# pearwatch-bottom.net
KiCad netlist of a schematic drawn in EAGLE
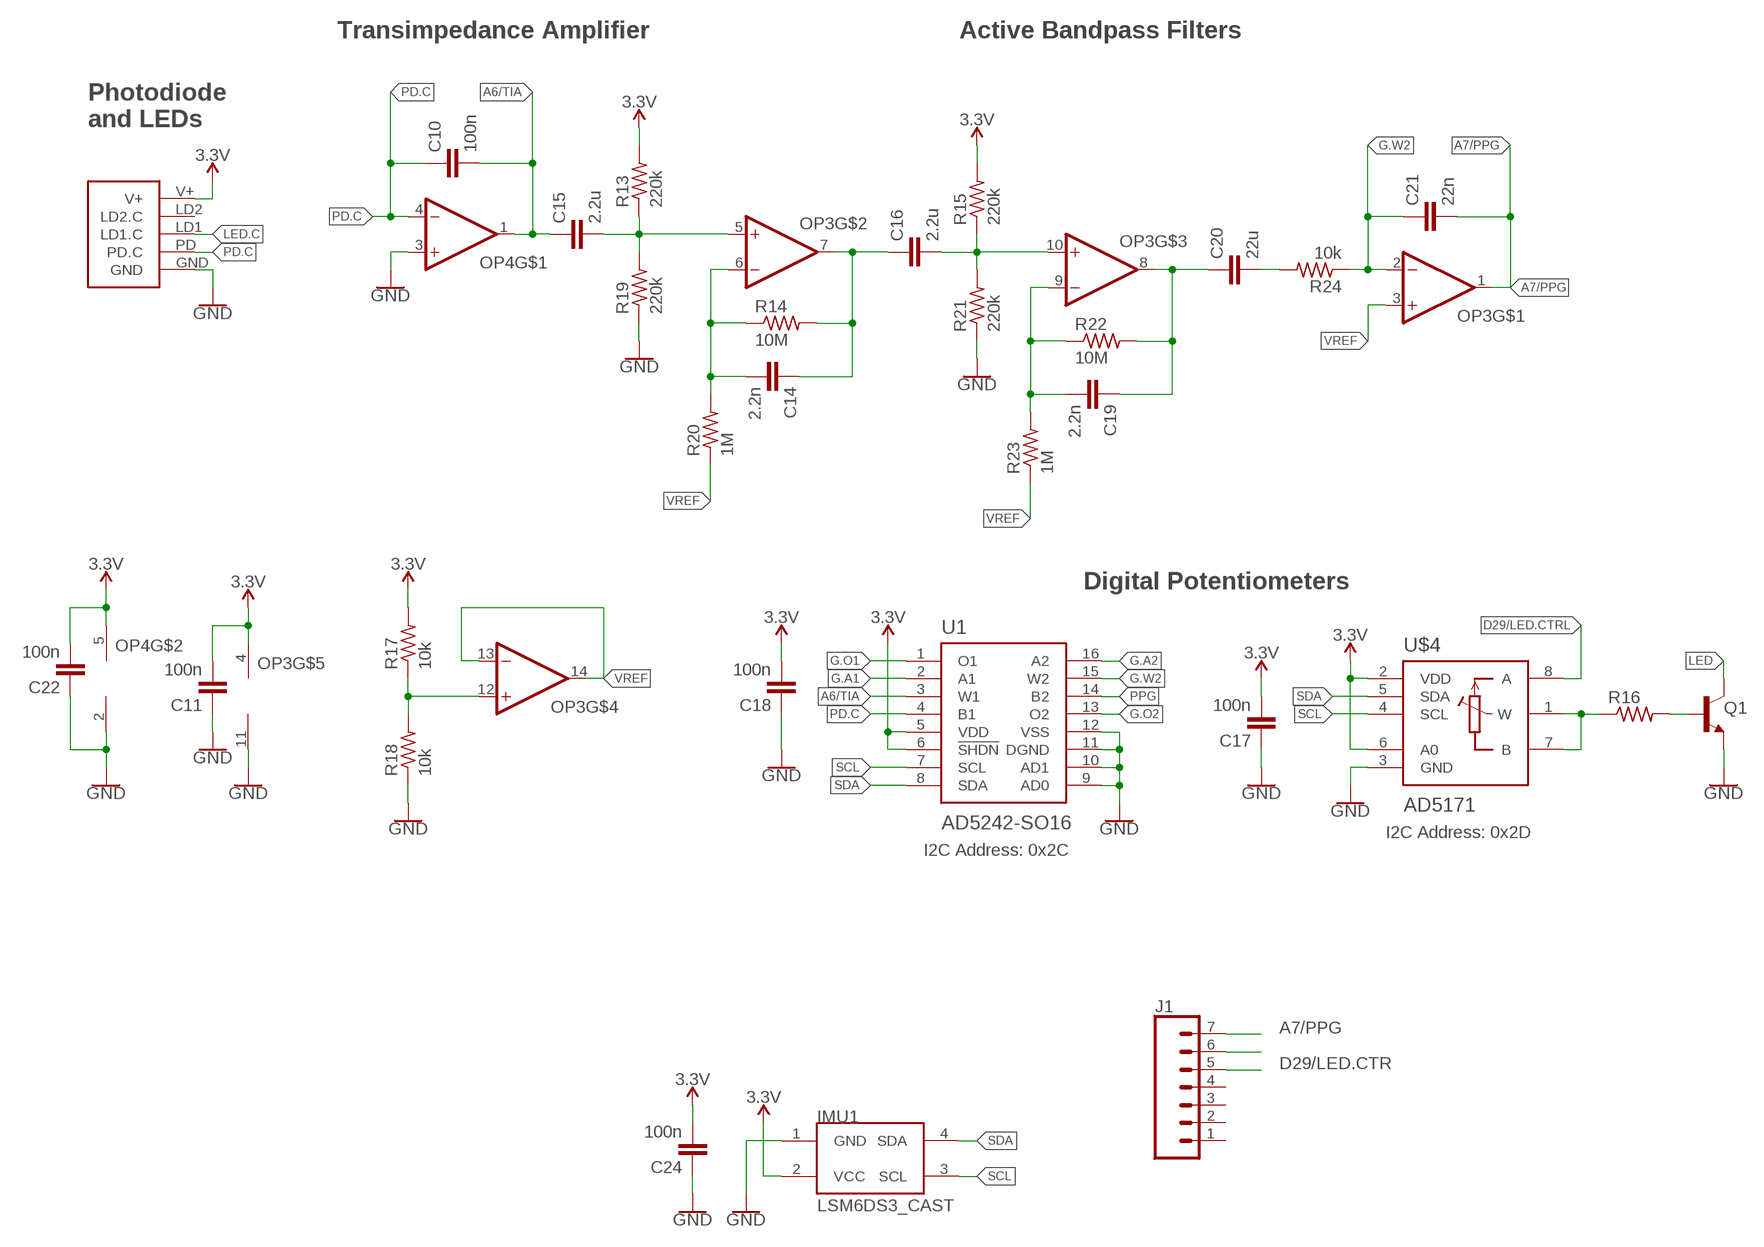
[diagram p0: schematic, sheet 1]

(export (version "E")
  (design (tool "Eeschema 10.0.6"))
  (components
    (comp (ref "C10")
      (value "100n")
      (footprint "eagle-import:C0603")
      (libsource (lib "eagle-import") (part "CAPACITOR0603"))
    )
    (comp (ref "C11")
      (value "100n")
      (footprint "eagle-import:C0603")
      (libsource (lib "eagle-import") (part "CAPACITOR0603"))
    )
    (comp (ref "C14")
      (value "2.2n")
      (footprint "eagle-import:C0603")
      (libsource (lib "eagle-import") (part "CAPACITOR0603"))
    )
    (comp (ref "C15")
      (value "2.2u")
      (footprint "eagle-import:C0603")
      (libsource (lib "eagle-import") (part "CAPACITOR0603"))
    )
    (comp (ref "C16")
      (value "2.2u")
      (footprint "eagle-import:C0603")
      (libsource (lib "eagle-import") (part "CAPACITOR0603"))
    )
    (comp (ref "C17")
      (value "100n")
      (footprint "eagle-import:C0603")
      (libsource (lib "eagle-import") (part "CAPACITOR0603"))
    )
    (comp (ref "C18")
      (value "100n")
      (footprint "eagle-import:C0603")
      (libsource (lib "eagle-import") (part "CAPACITOR0603"))
    )
    (comp (ref "C19")
      (value "2.2n")
      (footprint "eagle-import:C0603")
      (libsource (lib "eagle-import") (part "CAPACITOR0603"))
    )
    (comp (ref "C20")
      (value "22u")
      (footprint "eagle-import:C0603")
      (libsource (lib "eagle-import") (part "CAPACITOR0603"))
    )
    (comp (ref "C21")
      (value "22n")
      (footprint "eagle-import:C0603")
      (libsource (lib "eagle-import") (part "CAPACITOR0603"))
    )
    (comp (ref "C22")
      (value "100n")
      (footprint "eagle-import:C0603")
      (libsource (lib "eagle-import") (part "CAPACITOR0603"))
    )
    (comp (ref "C24")
      (value "100n")
      (footprint "eagle-import:C0603")
      (libsource (lib "eagle-import") (part "CAPACITOR0603"))
    )
    (comp (ref "IMU1")
      (value "LSM6DS3_CAST")
      (footprint "eagle-import:LSM6DS3_CAST")
      (libsource (lib "eagle-import") (part "LSM6DS3_CAST"))
    )
    (comp (ref "J1")
      (value "CONN_07")
      (footprint "eagle-import:1X07")
      (libsource (lib "eagle-import") (part "CONN_07"))
    )
    (comp (ref "OP3")
      (value "OP-QUAD-SO14")
      (footprint "eagle-import:SO14")
      (libsource (lib "eagle-import") (part "OP-QUAD-SO14"))
    )
    (comp (ref "OP4")
      (value "OP-SINGLEOT")
      (footprint "eagle-import:SOT23-5")
      (libsource (lib "eagle-import") (part "OP-SINGLEOT"))
    )
    (comp (ref "Q1")
      (value "NPN-GENERIC")
      (footprint "eagle-import:SOT23-3")
      (libsource (lib "eagle-import") (part "NPN-GENERIC"))
    )
    (comp (ref "R13")
      (value "220k")
      (footprint "eagle-import:R0603")
      (libsource (lib "eagle-import") (part "RESISTOR0603"))
    )
    (comp (ref "R14")
      (value "10M")
      (footprint "eagle-import:R0603")
      (libsource (lib "eagle-import") (part "RESISTOR0603"))
    )
    (comp (ref "R15")
      (value "220k")
      (footprint "eagle-import:R0603")
      (libsource (lib "eagle-import") (part "RESISTOR0603"))
    )
    (comp (ref "R16")
      (value "RESISTOR0603")
      (footprint "eagle-import:R0603")
      (libsource (lib "eagle-import") (part "RESISTOR0603"))
    )
    (comp (ref "R17")
      (value "10k")
      (footprint "eagle-import:R0402")
      (libsource (lib "eagle-import") (part "RESISTOR0402"))
    )
    (comp (ref "R18")
      (value "10k")
      (footprint "eagle-import:R0402")
      (libsource (lib "eagle-import") (part "RESISTOR0402"))
    )
    (comp (ref "R19")
      (value "220k")
      (footprint "eagle-import:R0603")
      (libsource (lib "eagle-import") (part "RESISTOR0603"))
    )
    (comp (ref "R20")
      (value "1M")
      (footprint "eagle-import:R0603")
      (libsource (lib "eagle-import") (part "RESISTOR0603"))
    )
    (comp (ref "R21")
      (value "220k")
      (footprint "eagle-import:R0603")
      (libsource (lib "eagle-import") (part "RESISTOR0603"))
    )
    (comp (ref "R22")
      (value "10M")
      (footprint "eagle-import:R0603")
      (libsource (lib "eagle-import") (part "RESISTOR0603"))
    )
    (comp (ref "R23")
      (value "1M")
      (footprint "eagle-import:R0603")
      (libsource (lib "eagle-import") (part "RESISTOR0603"))
    )
    (comp (ref "R24")
      (value "10k")
      (footprint "eagle-import:R0603")
      (libsource (lib "eagle-import") (part "RESISTOR0603"))
    )
    (comp (ref "U$3")
      (value "PPG.MODULE.2")
      (footprint "eagle-import:PPG.MODULE.2")
      (libsource (lib "eagle-import") (part "PPG.MODULE.2"))
    )
    (comp (ref "U$4")
      (value "AD5171")
      (footprint "eagle-import:SOT-23-8")
      (libsource (lib "eagle-import") (part "AD5171"))
    )
    (comp (ref "U1")
      (value "AD5242-SO16")
      (footprint "eagle-import:SO16")
      (libsource (lib "eagle-import") (part "AD5242-SO16"))
    )
  )
  (nets
    (net (code "1") (name "/D29{slash}LED.CTR") (class "Default")
      (node (ref "J1") (pin "6") (pinfunction "6_6") (pintype "passive"))
    )
    (net (code "2") (name "3.3V") (class "Default")
      (node (ref "C11") (pin "2") (pinfunction "2_2") (pintype "passive"))
      (node (ref "C17") (pin "2") (pinfunction "2_2") (pintype "passive"))
      (node (ref "C18") (pin "2") (pinfunction "2_2") (pintype "passive"))
      (node (ref "C22") (pin "2") (pinfunction "2_2") (pintype "passive"))
      (node (ref "C24") (pin "2") (pinfunction "2_2") (pintype "passive"))
      (node (ref "IMU1") (pin "2") (pinfunction "VCC_2") (pintype "bidirectional"))
      (node (ref "OP3") (pin "4") (pinfunction "V+_4") (pintype "power_in"))
      (node (ref "OP4") (pin "5") (pinfunction "V+_5") (pintype "power_in"))
      (node (ref "R13") (pin "2") (pinfunction "2_2") (pintype "passive"))
      (node (ref "R15") (pin "2") (pinfunction "2_2") (pintype "passive"))
      (node (ref "R17") (pin "2") (pinfunction "2_2") (pintype "passive"))
      (node (ref "U$3") (pin "V+") (pinfunction "V+_V+") (pintype "bidirectional"))
      (node (ref "U$4") (pin "2") (pinfunction "VDD_2") (pintype "bidirectional"))
      (node (ref "U$4") (pin "6") (pinfunction "A0_6") (pintype "bidirectional"))
      (node (ref "U1") (pin "5") (pinfunction "VDD_5") (pintype "bidirectional"))
      (node (ref "U1") (pin "6") (pinfunction "~{SHDN}_6") (pintype "bidirectional"))
    )
    (net (code "3") (name "A6{slash}TIA") (class "Default")
      (node (ref "C10") (pin "2") (pinfunction "2_2") (pintype "passive"))
      (node (ref "C15") (pin "1") (pinfunction "1_1") (pintype "passive"))
      (node (ref "J1") (pin "5") (pinfunction "5_5") (pintype "passive"))
      (node (ref "OP4") (pin "1") (pinfunction "OUT_1") (pintype "output"))
      (node (ref "U1") (pin "3") (pinfunction "W1_3") (pintype "bidirectional"))
    )
    (net (code "4") (name "A7{slash}PPG") (class "Default")
      (node (ref "C21") (pin "2") (pinfunction "2_2") (pintype "passive"))
      (node (ref "J1") (pin "7") (pinfunction "7_7") (pintype "passive"))
      (node (ref "OP3") (pin "1") (pinfunction "OUT_1") (pintype "output"))
    )
    (net (code "5") (name "D29{slash}LED.CTRL") (class "Default")
      (node (ref "U$4") (pin "8") (pinfunction "A_8") (pintype "bidirectional"))
    )
    (net (code "6") (name "G.A1") (class "Default")
      (node (ref "U1") (pin "2") (pinfunction "A1_2") (pintype "bidirectional"))
    )
    (net (code "7") (name "G.A2") (class "Default")
      (node (ref "U1") (pin "16") (pinfunction "A2_16") (pintype "bidirectional"))
    )
    (net (code "8") (name "G.O1") (class "Default")
      (node (ref "U1") (pin "1") (pinfunction "O1_1") (pintype "bidirectional"))
    )
    (net (code "9") (name "G.O2") (class "Default")
      (node (ref "U1") (pin "13") (pinfunction "O2_13") (pintype "bidirectional"))
    )
    (net (code "10") (name "G.W2") (class "Default")
      (node (ref "C21") (pin "1") (pinfunction "1_1") (pintype "passive"))
      (node (ref "OP3") (pin "2") (pinfunction "-IN_2") (pintype "input"))
      (node (ref "R24") (pin "1") (pinfunction "1_1") (pintype "passive"))
      (node (ref "U1") (pin "15") (pinfunction "W2_15") (pintype "bidirectional"))
    )
    (net (code "11") (name "GND") (class "Default")
      (node (ref "C11") (pin "1") (pinfunction "1_1") (pintype "passive"))
      (node (ref "C17") (pin "1") (pinfunction "1_1") (pintype "passive"))
      (node (ref "C18") (pin "1") (pinfunction "1_1") (pintype "passive"))
      (node (ref "C22") (pin "1") (pinfunction "1_1") (pintype "passive"))
      (node (ref "C24") (pin "1") (pinfunction "1_1") (pintype "passive"))
      (node (ref "IMU1") (pin "1") (pinfunction "GND_1") (pintype "bidirectional"))
      (node (ref "OP3") (pin "11") (pinfunction "V-_11") (pintype "power_in"))
      (node (ref "OP4") (pin "2") (pinfunction "V-_2") (pintype "power_in"))
      (node (ref "OP4") (pin "3") (pinfunction "+IN_3") (pintype "input"))
      (node (ref "Q1") (pin "2") (pinfunction "E_2") (pintype "passive"))
      (node (ref "R18") (pin "1") (pinfunction "1_1") (pintype "passive"))
      (node (ref "R19") (pin "1") (pinfunction "1_1") (pintype "passive"))
      (node (ref "R21") (pin "1") (pinfunction "1_1") (pintype "passive"))
      (node (ref "U$3") (pin "GND") (pinfunction "GND_GND") (pintype "bidirectional"))
      (node (ref "U$4") (pin "3") (pinfunction "GND_3") (pintype "bidirectional"))
      (node (ref "U1") (pin "10") (pinfunction "AD1_10") (pintype "bidirectional"))
      (node (ref "U1") (pin "11") (pinfunction "DGND_11") (pintype "bidirectional"))
      (node (ref "U1") (pin "12") (pinfunction "VSS_12") (pintype "bidirectional"))
      (node (ref "U1") (pin "9") (pinfunction "AD0_9") (pintype "bidirectional"))
    )
    (net (code "12") (name "LED") (class "Default")
      (node (ref "Q1") (pin "3") (pinfunction "C_3") (pintype "passive"))
    )
    (net (code "13") (name "LED.C") (class "Default")
      (node (ref "U$3") (pin "LD1") (pinfunction "LD1.C_LD1") (pintype "bidirectional"))
    )
    (net (code "14") (name "Net-(C20-Pad2)") (class "Default")
      (node (ref "C20") (pin "2") (pinfunction "2_2") (pintype "passive"))
      (node (ref "R24") (pin "2") (pinfunction "2_2") (pintype "passive"))
    )
    (net (code "15") (name "Net-(OP3B-+IN)") (class "Default")
      (node (ref "C15") (pin "2") (pinfunction "2_2") (pintype "passive"))
      (node (ref "OP3") (pin "5") (pinfunction "+IN_5") (pintype "input"))
      (node (ref "R13") (pin "1") (pinfunction "1_1") (pintype "passive"))
      (node (ref "R19") (pin "2") (pinfunction "2_2") (pintype "passive"))
    )
    (net (code "16") (name "Net-(OP3B--IN)") (class "Default")
      (node (ref "C14") (pin "2") (pinfunction "2_2") (pintype "passive"))
      (node (ref "OP3") (pin "6") (pinfunction "-IN_6") (pintype "input"))
      (node (ref "R14") (pin "1") (pinfunction "1_1") (pintype "passive"))
      (node (ref "R20") (pin "2") (pinfunction "2_2") (pintype "passive"))
    )
    (net (code "17") (name "Net-(OP3B-OUT)") (class "Default")
      (node (ref "C14") (pin "1") (pinfunction "1_1") (pintype "passive"))
      (node (ref "C16") (pin "1") (pinfunction "1_1") (pintype "passive"))
      (node (ref "OP3") (pin "7") (pinfunction "OUT_7") (pintype "output"))
      (node (ref "R14") (pin "2") (pinfunction "2_2") (pintype "passive"))
    )
    (net (code "18") (name "Net-(OP3C-+IN)") (class "Default")
      (node (ref "C16") (pin "2") (pinfunction "2_2") (pintype "passive"))
      (node (ref "OP3") (pin "10") (pinfunction "+IN_10") (pintype "input"))
      (node (ref "R15") (pin "1") (pinfunction "1_1") (pintype "passive"))
      (node (ref "R21") (pin "2") (pinfunction "2_2") (pintype "passive"))
    )
    (net (code "19") (name "Net-(OP3C--IN)") (class "Default")
      (node (ref "C19") (pin "2") (pinfunction "2_2") (pintype "passive"))
      (node (ref "OP3") (pin "9") (pinfunction "-IN_9") (pintype "input"))
      (node (ref "R22") (pin "1") (pinfunction "1_1") (pintype "passive"))
      (node (ref "R23") (pin "2") (pinfunction "2_2") (pintype "passive"))
    )
    (net (code "20") (name "Net-(OP3C-OUT)") (class "Default")
      (node (ref "C19") (pin "1") (pinfunction "1_1") (pintype "passive"))
      (node (ref "C20") (pin "1") (pinfunction "1_1") (pintype "passive"))
      (node (ref "OP3") (pin "8") (pinfunction "OUT_8") (pintype "output"))
      (node (ref "R22") (pin "2") (pinfunction "2_2") (pintype "passive"))
    )
    (net (code "21") (name "Net-(OP3D-+IN)") (class "Default")
      (node (ref "OP3") (pin "12") (pinfunction "+IN_12") (pintype "input"))
      (node (ref "R17") (pin "1") (pinfunction "1_1") (pintype "passive"))
      (node (ref "R18") (pin "2") (pinfunction "2_2") (pintype "passive"))
    )
    (net (code "22") (name "Net-(Q1-B)") (class "Default")
      (node (ref "Q1") (pin "1") (pinfunction "B_1") (pintype "passive"))
      (node (ref "R16") (pin "2") (pinfunction "2_2") (pintype "passive"))
    )
    (net (code "23") (name "Net-(U$4-B)") (class "Default")
      (node (ref "R16") (pin "1") (pinfunction "1_1") (pintype "passive"))
      (node (ref "U$4") (pin "1") (pinfunction "W_1") (pintype "bidirectional"))
      (node (ref "U$4") (pin "7") (pinfunction "B_7") (pintype "bidirectional"))
    )
    (net (code "24") (name "PD.C") (class "Default")
      (node (ref "C10") (pin "1") (pinfunction "1_1") (pintype "passive"))
      (node (ref "OP4") (pin "4") (pinfunction "-IN_4") (pintype "input"))
      (node (ref "U$3") (pin "PD") (pinfunction "PD.C_PD") (pintype "bidirectional"))
      (node (ref "U1") (pin "4") (pinfunction "B1_4") (pintype "bidirectional"))
    )
    (net (code "25") (name "PPG") (class "Default")
      (node (ref "U1") (pin "14") (pinfunction "B2_14") (pintype "bidirectional"))
    )
    (net (code "26") (name "SCL") (class "Default")
      (node (ref "IMU1") (pin "3") (pinfunction "SCL_3") (pintype "bidirectional"))
      (node (ref "U$4") (pin "4") (pinfunction "SCL_4") (pintype "bidirectional"))
      (node (ref "U1") (pin "7") (pinfunction "SCL_7") (pintype "bidirectional"))
    )
    (net (code "27") (name "SDA") (class "Default")
      (node (ref "IMU1") (pin "4") (pinfunction "SDA_4") (pintype "bidirectional"))
      (node (ref "U$4") (pin "5") (pinfunction "SDA_5") (pintype "bidirectional"))
      (node (ref "U1") (pin "8") (pinfunction "SDA_8") (pintype "bidirectional"))
    )
    (net (code "28") (name "VREF") (class "Default")
      (node (ref "OP3") (pin "13") (pinfunction "-IN_13") (pintype "input"))
      (node (ref "OP3") (pin "14") (pinfunction "OUT_14") (pintype "output"))
      (node (ref "OP3") (pin "3") (pinfunction "+IN_3") (pintype "input"))
      (node (ref "R20") (pin "1") (pinfunction "1_1") (pintype "passive"))
      (node (ref "R23") (pin "1") (pinfunction "1_1") (pintype "passive"))
    )
    (net (code "29") (name "unconnected-(J1-Pad1)") (class "Default")
      (node (ref "J1") (pin "1") (pinfunction "1_1") (pintype "passive"))
    )
    (net (code "30") (name "unconnected-(J1-Pad2)") (class "Default")
      (node (ref "J1") (pin "2") (pinfunction "2_2") (pintype "passive"))
    )
    (net (code "31") (name "unconnected-(J1-Pad3)") (class "Default")
      (node (ref "J1") (pin "3") (pinfunction "3_3") (pintype "passive"))
    )
    (net (code "32") (name "unconnected-(J1-Pad4)") (class "Default")
      (node (ref "J1") (pin "4") (pinfunction "4_4") (pintype "passive"))
    )
    (net (code "33") (name "unconnected-(U$3-LD2.C-PadLD2)") (class "Default")
      (node (ref "U$3") (pin "LD2") (pinfunction "LD2.C_LD2") (pintype "bidirectional"))
    )
  )
)
